# LED_String_NE2B757GT.net
KiCad netlist of a schematic drawn in Altium Designer
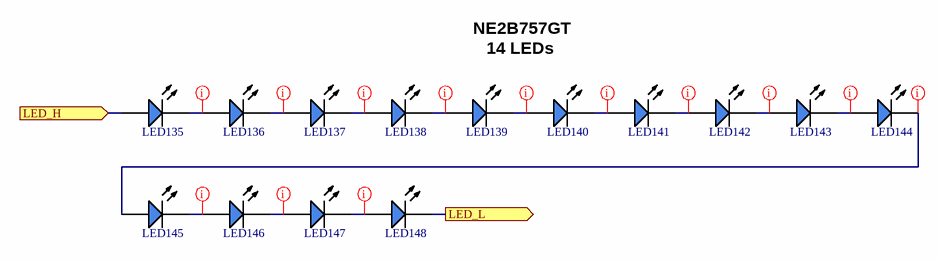
[diagram p0: LED_String_NE2B757GT.SchDoc]

(export (version "E")
  (design (tool "Eeschema 10.0.6"))
  (components
    (comp (ref "LED135")
      (value "NE2B757GT")
      (footprint "NE2B757GT")
      (description "SMD LED White 2,9 V, 8,7 lm 3030 (1212)")
      (fields (field (name "MANUFACTURER") "Nichia"))
      (libsource (lib "ETHZ Vault") (part "LED Blue"))
    )
    (comp (ref "LED136")
      (value "NE2B757GT")
      (footprint "NE2B757GT")
      (description "SMD LED White 2,9 V, 8,7 lm 3030 (1212)")
      (fields (field (name "MANUFACTURER") "Nichia"))
      (libsource (lib "ETHZ Vault") (part "LED Blue"))
    )
    (comp (ref "LED137")
      (value "NE2B757GT")
      (footprint "NE2B757GT")
      (description "SMD LED White 2,9 V, 8,7 lm 3030 (1212)")
      (fields (field (name "MANUFACTURER") "Nichia"))
      (libsource (lib "ETHZ Vault") (part "LED Blue"))
    )
    (comp (ref "LED138")
      (value "NE2B757GT")
      (footprint "NE2B757GT")
      (description "SMD LED White 2,9 V, 8,7 lm 3030 (1212)")
      (fields (field (name "MANUFACTURER") "Nichia"))
      (libsource (lib "ETHZ Vault") (part "LED Blue"))
    )
    (comp (ref "LED139")
      (value "NE2B757GT")
      (footprint "NE2B757GT")
      (description "SMD LED White 2,9 V, 8,7 lm 3030 (1212)")
      (fields (field (name "MANUFACTURER") "Nichia"))
      (libsource (lib "ETHZ Vault") (part "LED Blue"))
    )
    (comp (ref "LED140")
      (value "NE2B757GT")
      (footprint "NE2B757GT")
      (description "SMD LED White 2,9 V, 8,7 lm 3030 (1212)")
      (fields (field (name "MANUFACTURER") "Nichia"))
      (libsource (lib "ETHZ Vault") (part "LED Blue"))
    )
    (comp (ref "LED141")
      (value "NE2B757GT")
      (footprint "NE2B757GT")
      (description "SMD LED White 2,9 V, 8,7 lm 3030 (1212)")
      (fields (field (name "MANUFACTURER") "Nichia"))
      (libsource (lib "ETHZ Vault") (part "LED Blue"))
    )
    (comp (ref "LED142")
      (value "NE2B757GT")
      (footprint "NE2B757GT")
      (description "SMD LED White 2,9 V, 8,7 lm 3030 (1212)")
      (fields (field (name "MANUFACTURER") "Nichia"))
      (libsource (lib "ETHZ Vault") (part "LED Blue"))
    )
    (comp (ref "LED143")
      (value "NE2B757GT")
      (footprint "NE2B757GT")
      (description "SMD LED White 2,9 V, 8,7 lm 3030 (1212)")
      (fields (field (name "MANUFACTURER") "Nichia"))
      (libsource (lib "ETHZ Vault") (part "LED Blue"))
    )
    (comp (ref "LED144")
      (value "NE2B757GT")
      (footprint "NE2B757GT")
      (description "SMD LED White 2,9 V, 8,7 lm 3030 (1212)")
      (fields (field (name "MANUFACTURER") "Nichia"))
      (libsource (lib "ETHZ Vault") (part "LED Blue"))
    )
    (comp (ref "LED145")
      (value "NE2B757GT")
      (footprint "NE2B757GT")
      (description "SMD LED White 2,9 V, 8,7 lm 3030 (1212)")
      (fields (field (name "MANUFACTURER") "Nichia"))
      (libsource (lib "ETHZ Vault") (part "LED Blue"))
    )
    (comp (ref "LED146")
      (value "NE2B757GT")
      (footprint "NE2B757GT")
      (description "SMD LED White 2,9 V, 8,7 lm 3030 (1212)")
      (fields (field (name "MANUFACTURER") "Nichia"))
      (libsource (lib "ETHZ Vault") (part "LED Blue"))
    )
    (comp (ref "LED147")
      (value "NE2B757GT")
      (footprint "NE2B757GT")
      (description "SMD LED White 2,9 V, 8,7 lm 3030 (1212)")
      (fields (field (name "MANUFACTURER") "Nichia"))
      (libsource (lib "ETHZ Vault") (part "LED Blue"))
    )
    (comp (ref "LED148")
      (value "NE2B757GT")
      (footprint "NE2B757GT")
      (description "SMD LED White 2,9 V, 8,7 lm 3030 (1212)")
      (fields (field (name "MANUFACTURER") "Nichia"))
      (libsource (lib "ETHZ Vault") (part "LED Blue"))
    )
  )
  (nets
    (net (code "1") (name "/LED_H") (class "Default")
      (node (ref "LED135") (pin "2") (pinfunction "A_2") (pintype "passive"))
    )
    (net (code "2") (name "/LED_L") (class "Default")
      (node (ref "LED148") (pin "1") (pinfunction "K_1") (pintype "passive"))
    )
    (net (code "3") (name "Net-(LED135-K)") (class "Default")
      (node (ref "LED135") (pin "1") (pinfunction "K_1") (pintype "passive"))
      (node (ref "LED136") (pin "2") (pinfunction "A_2") (pintype "passive"))
    )
    (net (code "4") (name "Net-(LED136-K)") (class "Default")
      (node (ref "LED136") (pin "1") (pinfunction "K_1") (pintype "passive"))
      (node (ref "LED137") (pin "2") (pinfunction "A_2") (pintype "passive"))
    )
    (net (code "5") (name "Net-(LED137-K)") (class "Default")
      (node (ref "LED137") (pin "1") (pinfunction "K_1") (pintype "passive"))
      (node (ref "LED138") (pin "2") (pinfunction "A_2") (pintype "passive"))
    )
    (net (code "6") (name "Net-(LED138-K)") (class "Default")
      (node (ref "LED138") (pin "1") (pinfunction "K_1") (pintype "passive"))
      (node (ref "LED139") (pin "2") (pinfunction "A_2") (pintype "passive"))
    )
    (net (code "7") (name "Net-(LED139-K)") (class "Default")
      (node (ref "LED139") (pin "1") (pinfunction "K_1") (pintype "passive"))
      (node (ref "LED140") (pin "2") (pinfunction "A_2") (pintype "passive"))
    )
    (net (code "8") (name "Net-(LED140-K)") (class "Default")
      (node (ref "LED140") (pin "1") (pinfunction "K_1") (pintype "passive"))
      (node (ref "LED141") (pin "2") (pinfunction "A_2") (pintype "passive"))
    )
    (net (code "9") (name "Net-(LED141-K)") (class "Default")
      (node (ref "LED141") (pin "1") (pinfunction "K_1") (pintype "passive"))
      (node (ref "LED142") (pin "2") (pinfunction "A_2") (pintype "passive"))
    )
    (net (code "10") (name "Net-(LED142-K)") (class "Default")
      (node (ref "LED142") (pin "1") (pinfunction "K_1") (pintype "passive"))
      (node (ref "LED143") (pin "2") (pinfunction "A_2") (pintype "passive"))
    )
    (net (code "11") (name "Net-(LED143-K)") (class "Default")
      (node (ref "LED143") (pin "1") (pinfunction "K_1") (pintype "passive"))
      (node (ref "LED144") (pin "2") (pinfunction "A_2") (pintype "passive"))
    )
    (net (code "12") (name "Net-(LED144-K)") (class "Default")
      (node (ref "LED144") (pin "1") (pinfunction "K_1") (pintype "passive"))
      (node (ref "LED145") (pin "2") (pinfunction "A_2") (pintype "passive"))
    )
    (net (code "13") (name "Net-(LED145-K)") (class "Default")
      (node (ref "LED145") (pin "1") (pinfunction "K_1") (pintype "passive"))
      (node (ref "LED146") (pin "2") (pinfunction "A_2") (pintype "passive"))
    )
    (net (code "14") (name "Net-(LED146-K)") (class "Default")
      (node (ref "LED146") (pin "1") (pinfunction "K_1") (pintype "passive"))
      (node (ref "LED147") (pin "2") (pinfunction "A_2") (pintype "passive"))
    )
    (net (code "15") (name "Net-(LED147-K)") (class "Default")
      (node (ref "LED147") (pin "1") (pinfunction "K_1") (pintype "passive"))
      (node (ref "LED148") (pin "2") (pinfunction "A_2") (pintype "passive"))
    )
  )
)
